# CLP_v1_2_Sch1.net
KiCad netlist of a schematic drawn in Altium Designer
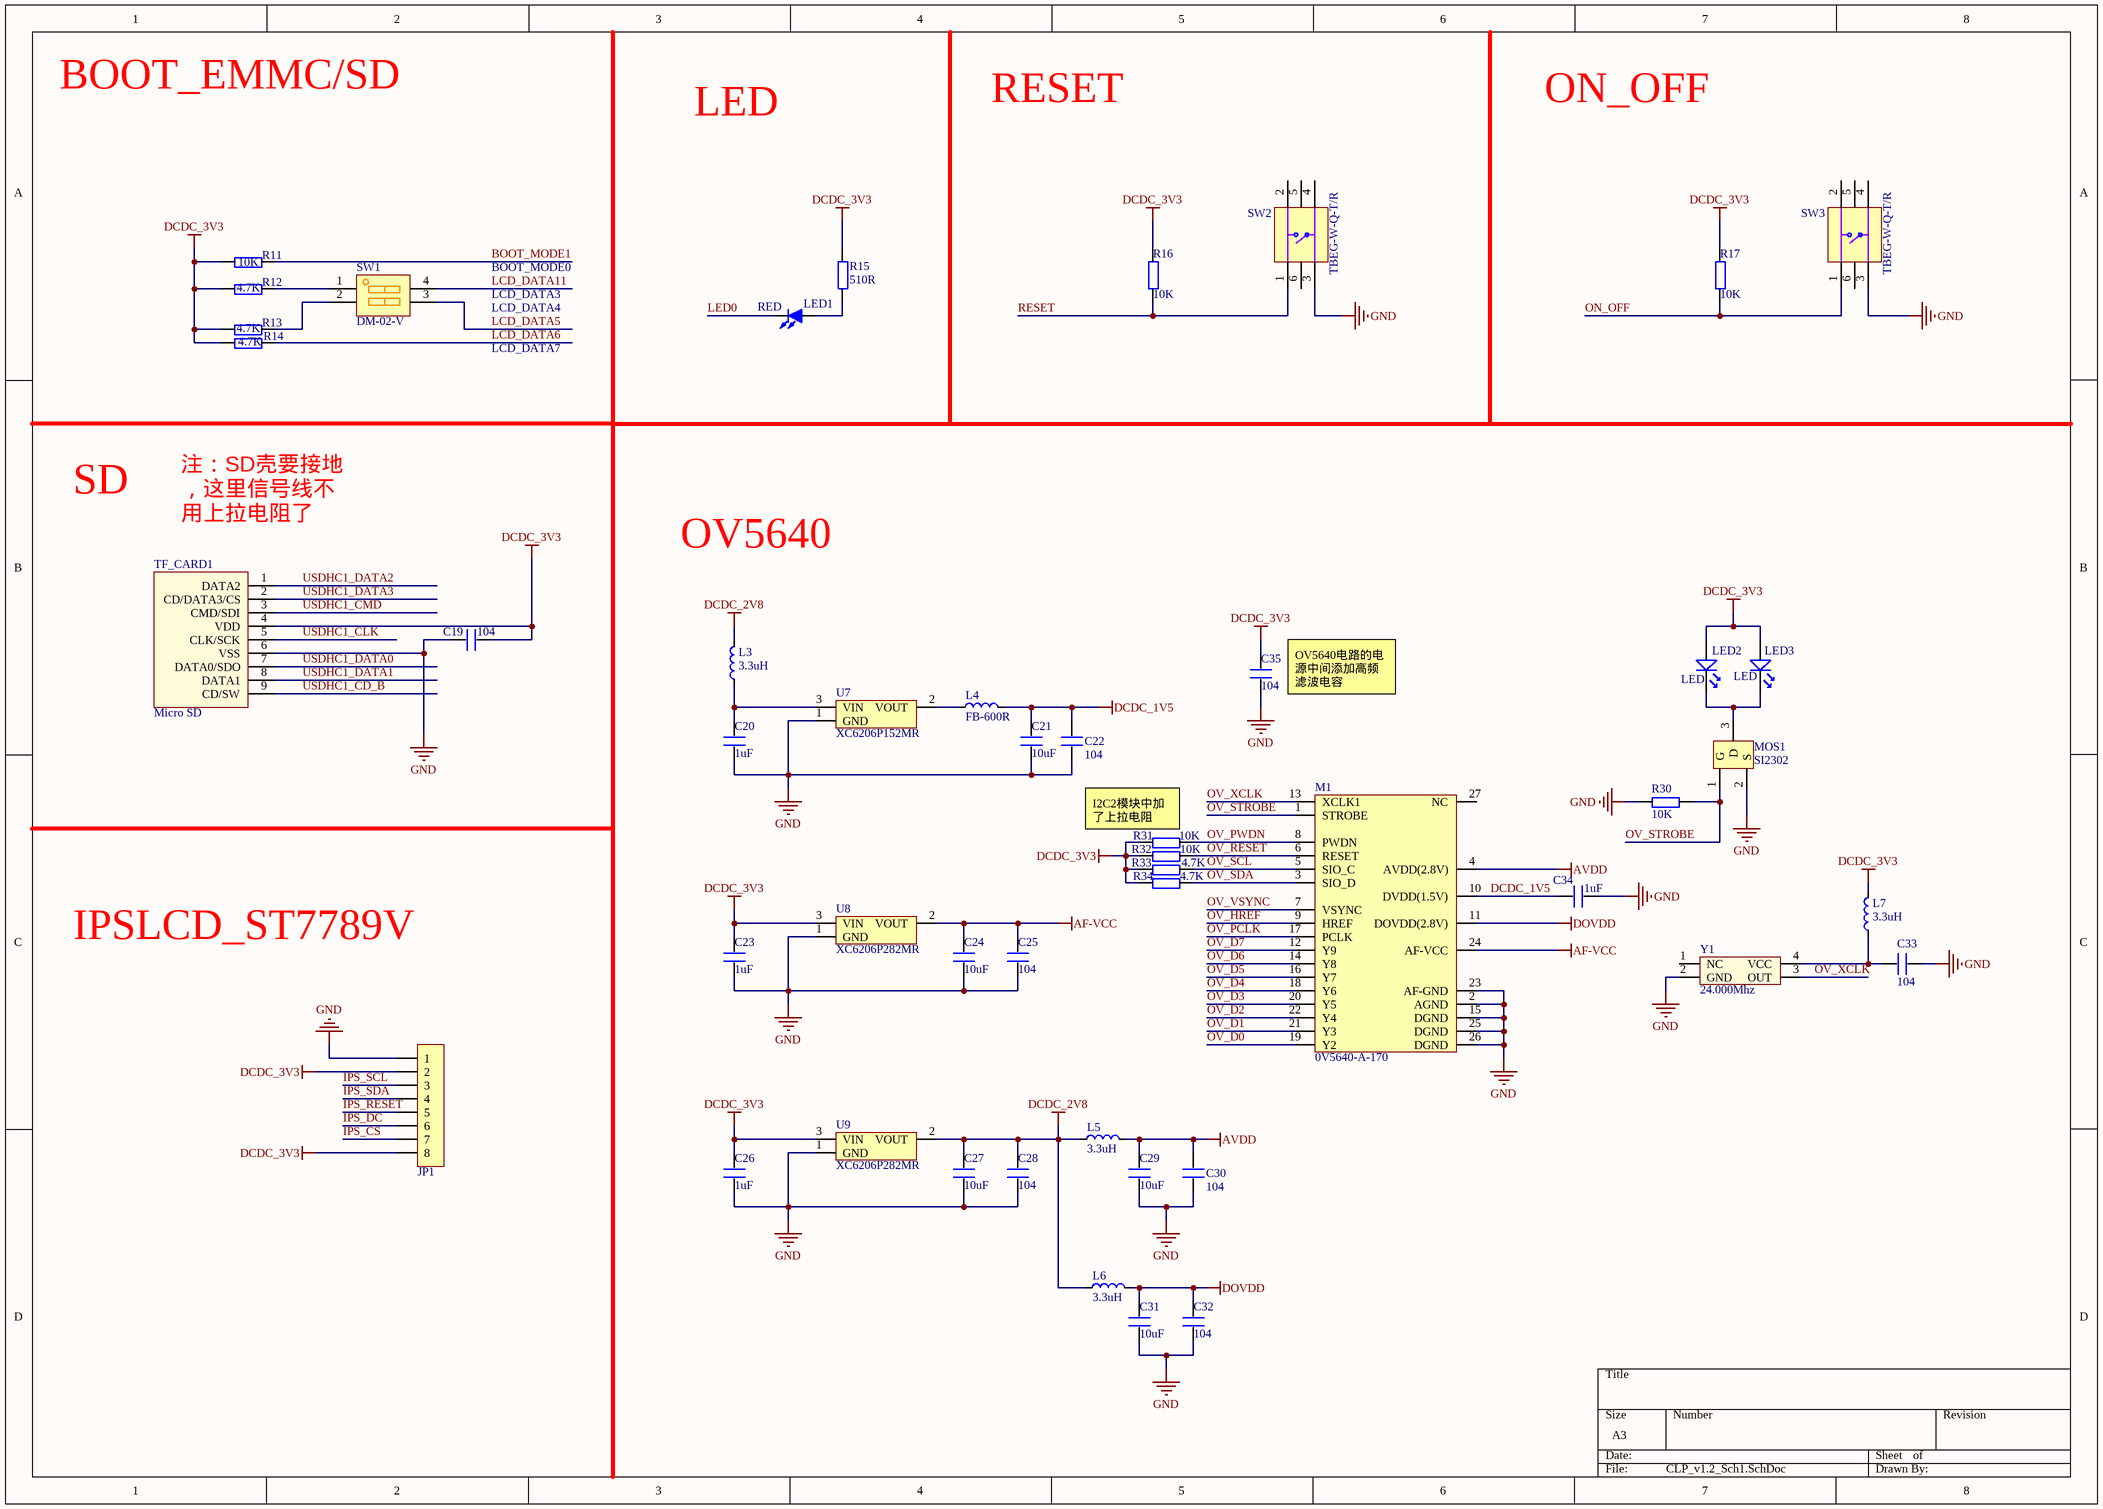
[diagram p0: CLP_v1.2_Sch1.SchDoc]

(export (version "E")
  (design (tool "Eeschema 10.0.6"))
  (components
    (comp (ref "C19") (value "104") (footprint "C 0603") (libsource (lib "IMX6UL_ALPHA(底板)_V2.0") (part "C")))
    (comp (ref "C20") (value "1uF") (footprint "C 0603") (libsource (lib "IMX6UL_ALPHA(底板)_V2.0") (part "C")))
    (comp (ref "C21")
      (value "10uF")
      (footprint "C 0603")
      (libsource (lib "IMX6UL_ALPHA(底板)_V2.0") (part "C"))
    )
    (comp (ref "C22") (value "104") (footprint "C 0603") (libsource (lib "IMX6UL_ALPHA(底板)_V2.0") (part "C")))
    (comp (ref "C23") (value "1uF") (footprint "C 0603") (libsource (lib "IMX6UL_ALPHA(底板)_V2.0") (part "C")))
    (comp (ref "C24")
      (value "10uF")
      (footprint "C 0603")
      (libsource (lib "IMX6UL_ALPHA(底板)_V2.0") (part "C"))
    )
    (comp (ref "C25") (value "104") (footprint "C 0603") (libsource (lib "IMX6UL_ALPHA(底板)_V2.0") (part "C")))
    (comp (ref "C26") (value "1uF") (footprint "C 0603") (libsource (lib "IMX6UL_ALPHA(底板)_V2.0") (part "C")))
    (comp (ref "C27")
      (value "10uF")
      (footprint "C 0603")
      (libsource (lib "IMX6UL_ALPHA(底板)_V2.0") (part "C"))
    )
    (comp (ref "C28") (value "104") (footprint "C 0603") (libsource (lib "IMX6UL_ALPHA(底板)_V2.0") (part "C")))
    (comp (ref "C29")
      (value "10uF")
      (footprint "C 0603")
      (libsource (lib "IMX6UL_ALPHA(底板)_V2.0") (part "C"))
    )
    (comp (ref "C30") (value "104") (footprint "C 0603") (libsource (lib "IMX6UL_ALPHA(底板)_V2.0") (part "C")))
    (comp (ref "C31")
      (value "10uF")
      (footprint "C 0603")
      (libsource (lib "IMX6UL_ALPHA(底板)_V2.0") (part "C"))
    )
    (comp (ref "C32") (value "104") (footprint "C 0603") (libsource (lib "IMX6UL_ALPHA(底板)_V2.0") (part "C")))
    (comp (ref "C33") (value "104") (footprint "C 0603") (libsource (lib "IMX6UL_ALPHA(底板)_V2.0") (part "C")))
    (comp (ref "C34") (value "1uF") (footprint "C 0603") (libsource (lib "IMX6UL_ALPHA(底板)_V2.0") (part "C")))
    (comp (ref "C35") (value "104") (footprint "C 0603") (libsource (lib "IMX6UL_ALPHA(底板)_V2.0") (part "C")))
    (comp (ref "JP1")
      (value "HDR-1X8")
      (footprint "HDR-1X8_M")
      (description "8P接插件")
      (fields (field (name "版权归属") "黎明电子style"))
      (libsource (lib "排针_排母") (part "Header 8"))
    )
    (comp (ref "L3")
      (value "3.3uH")
      (footprint "L 0603")
      (description "小功率贴片电感磁珠")
      (fields (field (name "版权归属") "源创客"))
      (libsource (lib "IMX6UL_ALPHA(底板)_V2.0") (part "L"))
    )
    (comp (ref "L4")
      (value "FB-600R")
      (footprint "L 0603")
      (description "小功率贴片电感磁珠")
      (fields (field (name "版权归属") "源创客"))
      (libsource (lib "IMX6UL_ALPHA(底板)_V2.0") (part "L"))
    )
    (comp (ref "L5")
      (value "3.3uH")
      (footprint "L 0603")
      (description "小功率贴片电感磁珠")
      (fields (field (name "版权归属") "源创客"))
      (libsource (lib "IMX6UL_ALPHA(底板)_V2.0") (part "L"))
    )
    (comp (ref "L6")
      (value "3.3uH")
      (footprint "L 0603")
      (description "小功率贴片电感磁珠")
      (fields (field (name "版权归属") "源创客"))
      (libsource (lib "IMX6UL_ALPHA(底板)_V2.0") (part "L"))
    )
    (comp (ref "L7")
      (value "3.3uH")
      (footprint "L 0603")
      (description "小功率贴片电感磁珠")
      (fields (field (name "版权归属") "源创客"))
      (libsource (lib "IMX6UL_ALPHA(底板)_V2.0") (part "L"))
    )
    (comp (ref "LED1")
      (value "RED")
      (footprint "LED 0805R")
      (description "贴片LED")
      (fields (field (name "版权归属") "源创客"))
      (libsource (lib "IMX6UL_ALPHA(底板)_V2.0") (part "LED-SMD"))
    )
    (comp (ref "LED2") (value "LED") (footprint "SMDLED-3528") (libsource (lib "OV5460") (part "LED")))
    (comp (ref "LED3") (value "LED") (footprint "SMDLED-3528") (libsource (lib "OV5460") (part "LED")))
    (comp (ref "M1")
      (value "0V5640-A-170")
      (footprint "OV5640")
      (description "OV5640-A-170,AF,FPC")
      (libsource (lib "OV5460") (part "OV5640-A-170"))
    )
    (comp (ref "MOS1")
      (value "SI2302")
      (footprint "SO-G3/C2.5")
      (description "AP2306")
      (libsource (lib "OV5460") (part "MOS-N"))
    )
    (comp (ref "R11") (value "10K") (footprint "R 0603") (libsource (lib "IMX6UL_ALPHA(底板)_V2.0") (part "R")))
    (comp (ref "R12")
      (value "4.7K")
      (footprint "R 0603")
      (libsource (lib "IMX6UL_ALPHA(底板)_V2.0") (part "R"))
    )
    (comp (ref "R13")
      (value "4.7K")
      (footprint "R 0603")
      (libsource (lib "IMX6UL_ALPHA(底板)_V2.0") (part "R"))
    )
    (comp (ref "R14")
      (value "4.7K")
      (footprint "R 0603")
      (libsource (lib "IMX6UL_ALPHA(底板)_V2.0") (part "R"))
    )
    (comp (ref "R15")
      (value "510R")
      (footprint "R 0603")
      (libsource (lib "IMX6UL_ALPHA(底板)_V2.0") (part "R"))
    )
    (comp (ref "R16") (value "10K") (footprint "R 0603") (libsource (lib "IMX6UL_ALPHA(底板)_V2.0") (part "R")))
    (comp (ref "R17") (value "10K") (footprint "R 0603") (libsource (lib "IMX6UL_ALPHA(底板)_V2.0") (part "R")))
    (comp (ref "R30") (value "10K") (footprint "R 0603") (libsource (lib "IMX6UL_ALPHA(底板)_V2.0") (part "R")))
    (comp (ref "R31") (value "10K") (footprint "R 0603") (libsource (lib "IMX6UL_ALPHA(底板)_V2.0") (part "R")))
    (comp (ref "R32") (value "10K") (footprint "R 0603") (libsource (lib "IMX6UL_ALPHA(底板)_V2.0") (part "R")))
    (comp (ref "R33")
      (value "4.7K")
      (footprint "R 0603")
      (libsource (lib "IMX6UL_ALPHA(底板)_V2.0") (part "R"))
    )
    (comp (ref "R34")
      (value "4.7K")
      (footprint "R 0603")
      (libsource (lib "IMX6UL_ALPHA(底板)_V2.0") (part "R"))
    )
    (comp (ref "SW1")
      (value "DM-02-V")
      (footprint "SMD_KEY")
      (description "boot && led key")
      (libsource (lib "CLP_v1.2_SchLib") (part "SMD_KEY"))
    )
    (comp (ref "SW2")
      (value "TBEG-W-Q-T/R")
      (footprint "SW")
      (description "key")
      (libsource (lib "CLP_v1.2_SchLib") (part "SW"))
    )
    (comp (ref "SW3")
      (value "TBEG-W-Q-T/R")
      (footprint "SW")
      (description "key")
      (libsource (lib "CLP_v1.2_SchLib") (part "SW"))
    )
    (comp (ref "TF_CARD1")
      (value "Micro SD")
      (footprint "Micro SD")
      (description "Micro SD卡")
      (fields (field (name "版权归属") "源创客"))
      (libsource (lib "IMX6UL_ALPHA(底板)_V2.0") (part "Micro SD"))
    )
    (comp (ref "U7")
      (value "XC6206P152MR")
      (footprint "SOT-23")
      (description "LDO,SOT23,1.2~5.0V")
      (libsource (lib "OV5460") (part "XC6206"))
    )
    (comp (ref "U8")
      (value "XC6206P282MR")
      (footprint "SOT-23")
      (description "LDO,SOT23,1.2~5.0V")
      (libsource (lib "OV5460") (part "XC6206"))
    )
    (comp (ref "U9")
      (value "XC6206P282MR")
      (footprint "SOT-23")
      (description "LDO,SOT23,1.2~5.0V")
      (libsource (lib "OV5460") (part "XC6206"))
    )
    (comp (ref "Y1")
      (value "24.000Mhz")
      (footprint "XTAL3225")
      (description "有源晶振")
      (libsource (lib "OV5460") (part "XTAL_S"))
    )
  )
  (nets
    (net (code "1") (name "/BOOT_MODE1") (class "Default") (node (ref "R11") (pin "2") (pintype "passive")))
    (net (code "2") (name "/IPS_CS") (class "Default")
      (node (ref "JP1") (pin "7") (pinfunction "7_7") (pintype "passive"))
    )
    (net (code "3") (name "/IPS_DC") (class "Default")
      (node (ref "JP1") (pin "6") (pinfunction "6_6") (pintype "passive"))
    )
    (net (code "4") (name "/IPS_RESET") (class "Default")
      (node (ref "JP1") (pin "5") (pinfunction "5_5") (pintype "passive"))
    )
    (net (code "5") (name "/IPS_SCL") (class "Default")
      (node (ref "JP1") (pin "3") (pinfunction "3_3") (pintype "passive"))
    )
    (net (code "6") (name "/IPS_SDA") (class "Default")
      (node (ref "JP1") (pin "4") (pinfunction "4_4") (pintype "passive"))
    )
    (net (code "7") (name "/LCD_DATA5") (class "Default")
      (node (ref "SW1") (pin "3") (pinfunction "3_3") (pintype "passive"))
    )
    (net (code "8") (name "/LCD_DATA6") (class "Default") (node (ref "R14") (pin "2") (pintype "passive")))
    (net (code "9") (name "/LCD_DATA11") (class "Default")
      (node (ref "SW1") (pin "4") (pinfunction "4_4") (pintype "passive"))
    )
    (net (code "10") (name "/LED0") (class "Default")
      (node (ref "LED1") (pin "2") (pinfunction "K_2") (pintype "passive"))
    )
    (net (code "11") (name "/ON_OFF") (class "Default")
      (node (ref "R17") (pin "1") (pintype "passive"))
      (node (ref "SW3") (pin "1") (pinfunction "1_1") (pintype "passive"))
    )
    (net (code "12") (name "/OV_D0") (class "Default")
      (node (ref "M1") (pin "19") (pinfunction "Y2_19") (pintype "passive"))
    )
    (net (code "13") (name "/OV_D1") (class "Default")
      (node (ref "M1") (pin "21") (pinfunction "Y3_21") (pintype "passive"))
    )
    (net (code "14") (name "/OV_D2") (class "Default")
      (node (ref "M1") (pin "22") (pinfunction "Y4_22") (pintype "passive"))
    )
    (net (code "15") (name "/OV_D3") (class "Default")
      (node (ref "M1") (pin "20") (pinfunction "Y5_20") (pintype "passive"))
    )
    (net (code "16") (name "/OV_D4") (class "Default")
      (node (ref "M1") (pin "18") (pinfunction "Y6_18") (pintype "passive"))
    )
    (net (code "17") (name "/OV_D5") (class "Default")
      (node (ref "M1") (pin "16") (pinfunction "Y7_16") (pintype "passive"))
    )
    (net (code "18") (name "/OV_D6") (class "Default")
      (node (ref "M1") (pin "14") (pinfunction "Y8_14") (pintype "passive"))
    )
    (net (code "19") (name "/OV_D7") (class "Default")
      (node (ref "M1") (pin "12") (pinfunction "Y9_12") (pintype "passive"))
    )
    (net (code "20") (name "/OV_HREF") (class "Default")
      (node (ref "M1") (pin "9") (pinfunction "HREF_9") (pintype "passive"))
    )
    (net (code "21") (name "/OV_PCLK") (class "Default")
      (node (ref "M1") (pin "17") (pinfunction "PCLK_17") (pintype "passive"))
    )
    (net (code "22") (name "/OV_PWDN") (class "Default")
      (node (ref "M1") (pin "8") (pinfunction "PWDN_8") (pintype "passive"))
      (node (ref "R31") (pin "2") (pintype "passive"))
    )
    (net (code "23") (name "/OV_RESET") (class "Default")
      (node (ref "M1") (pin "6") (pinfunction "RESET_6") (pintype "passive"))
      (node (ref "R32") (pin "2") (pintype "passive"))
    )
    (net (code "24") (name "/OV_SCL") (class "Default")
      (node (ref "M1") (pin "5") (pinfunction "SIO_C_5") (pintype "passive"))
      (node (ref "R33") (pin "2") (pintype "passive"))
    )
    (net (code "25") (name "/OV_SDA") (class "Default")
      (node (ref "M1") (pin "3") (pinfunction "SIO_D_3") (pintype "passive"))
      (node (ref "R34") (pin "2") (pintype "passive"))
    )
    (net (code "26") (name "/OV_STROBE") (class "Default")
      (node (ref "M1") (pin "1") (pinfunction "STROBE_1") (pintype "passive"))
      (node (ref "MOS1") (pin "1") (pinfunction "G_1") (pintype "passive"))
      (node (ref "R30") (pin "2") (pintype "passive"))
    )
    (net (code "27") (name "/OV_VSYNC") (class "Default")
      (node (ref "M1") (pin "7") (pinfunction "VSYNC_7") (pintype "passive"))
    )
    (net (code "28") (name "/OV_XCLK") (class "Default")
      (node (ref "M1") (pin "13") (pinfunction "XCLK1_13") (pintype "passive"))
      (node (ref "Y1") (pin "3") (pinfunction "OUT_3") (pintype "passive"))
    )
    (net (code "29") (name "/RESET") (class "Default")
      (node (ref "R16") (pin "1") (pintype "passive"))
      (node (ref "SW2") (pin "1") (pinfunction "1_1") (pintype "passive"))
    )
    (net (code "30") (name "/USDHC1_CD_B") (class "Default")
      (node (ref "TF_CARD1") (pin "9") (pinfunction "CD/SW_9") (pintype "passive"))
    )
    (net (code "31") (name "/USDHC1_CLK") (class "Default")
      (node (ref "TF_CARD1") (pin "5") (pinfunction "CLK/SCK_5") (pintype "passive"))
    )
    (net (code "32") (name "/USDHC1_CMD") (class "Default")
      (node (ref "TF_CARD1") (pin "3") (pinfunction "CMD/SDI_3") (pintype "passive"))
    )
    (net (code "33") (name "/USDHC1_DATA0") (class "Default")
      (node (ref "TF_CARD1") (pin "7") (pinfunction "DATA0/SDO_7") (pintype "passive"))
    )
    (net (code "34") (name "/USDHC1_DATA1") (class "Default")
      (node (ref "TF_CARD1") (pin "8") (pinfunction "DATA1_8") (pintype "passive"))
    )
    (net (code "35") (name "/USDHC1_DATA2") (class "Default")
      (node (ref "TF_CARD1") (pin "1") (pinfunction "DATA2_1") (pintype "passive"))
    )
    (net (code "36") (name "/USDHC1_DATA3") (class "Default")
      (node (ref "TF_CARD1") (pin "2") (pinfunction "CD/DATA3/CS_2") (pintype "passive"))
    )
    (net (code "37") (name "AF-VCC") (class "Default")
      (node (ref "C24") (pin "2") (pintype "passive"))
      (node (ref "C25") (pin "2") (pintype "passive"))
      (node (ref "M1") (pin "24") (pinfunction "AF-VCC_24") (pintype "passive"))
      (node (ref "U8") (pin "2") (pinfunction "VOUT_2") (pintype "passive"))
    )
    (net (code "38") (name "AVDD") (class "Default")
      (node (ref "C29") (pin "2") (pintype "passive"))
      (node (ref "C30") (pin "2") (pintype "passive"))
      (node (ref "L5") (pin "2") (pinfunction "2_2") (pintype "passive"))
      (node (ref "M1") (pin "4") (pinfunction "AVDD(2.8V)_4") (pintype "passive"))
    )
    (net (code "39") (name "DCDC_1V5") (class "Default")
      (node (ref "C21") (pin "2") (pintype "passive"))
      (node (ref "C22") (pin "2") (pintype "passive"))
      (node (ref "C34") (pin "1") (pintype "passive"))
      (node (ref "L4") (pin "2") (pinfunction "2_2") (pintype "passive"))
      (node (ref "M1") (pin "10") (pinfunction "DVDD(1.5V)_10") (pintype "passive"))
    )
    (net (code "40") (name "DCDC_2V8") (class "Default")
      (node (ref "C27") (pin "2") (pintype "passive"))
      (node (ref "C28") (pin "2") (pintype "passive"))
      (node (ref "L3") (pin "2") (pinfunction "2_2") (pintype "passive"))
      (node (ref "L5") (pin "1") (pinfunction "1_1") (pintype "passive"))
      (node (ref "L6") (pin "1") (pinfunction "1_1") (pintype "passive"))
      (node (ref "U9") (pin "2") (pinfunction "VOUT_2") (pintype "passive"))
    )
    (net (code "41") (name "DCDC_3V3") (class "Default")
      (node (ref "C19") (pin "2") (pintype "passive"))
      (node (ref "C23") (pin "2") (pintype "passive"))
      (node (ref "C26") (pin "2") (pintype "passive"))
      (node (ref "C35") (pin "2") (pintype "passive"))
      (node (ref "JP1") (pin "2") (pinfunction "2_2") (pintype "passive"))
      (node (ref "JP1") (pin "8") (pinfunction "8_8") (pintype "passive"))
      (node (ref "L7") (pin "2") (pinfunction "2_2") (pintype "passive"))
      (node (ref "LED2") (pin "1") (pinfunction "1_1") (pintype "passive"))
      (node (ref "LED3") (pin "1") (pinfunction "1_1") (pintype "passive"))
      (node (ref "R11") (pin "1") (pintype "passive"))
      (node (ref "R12") (pin "1") (pintype "passive"))
      (node (ref "R13") (pin "1") (pintype "passive"))
      (node (ref "R14") (pin "1") (pintype "passive"))
      (node (ref "R15") (pin "2") (pintype "passive"))
      (node (ref "R16") (pin "2") (pintype "passive"))
      (node (ref "R17") (pin "2") (pintype "passive"))
      (node (ref "R31") (pin "1") (pintype "passive"))
      (node (ref "R32") (pin "1") (pintype "passive"))
      (node (ref "R33") (pin "1") (pintype "passive"))
      (node (ref "R34") (pin "1") (pintype "passive"))
      (node (ref "TF_CARD1") (pin "4") (pinfunction "VDD_4") (pintype "passive"))
      (node (ref "U8") (pin "3") (pinfunction "VIN_3") (pintype "passive"))
      (node (ref "U9") (pin "3") (pinfunction "VIN_3") (pintype "passive"))
    )
    (net (code "42") (name "DOVDD") (class "Default")
      (node (ref "C31") (pin "2") (pintype "passive"))
      (node (ref "C32") (pin "2") (pintype "passive"))
      (node (ref "L6") (pin "2") (pinfunction "2_2") (pintype "passive"))
      (node (ref "M1") (pin "11") (pinfunction "DOVDD(2.8V)_11") (pintype "passive"))
    )
    (net (code "43") (name "GND") (class "Default")
      (node (ref "C19") (pin "1") (pintype "passive"))
      (node (ref "C20") (pin "1") (pintype "passive"))
      (node (ref "C21") (pin "1") (pintype "passive"))
      (node (ref "C22") (pin "1") (pintype "passive"))
      (node (ref "C23") (pin "1") (pintype "passive"))
      (node (ref "C24") (pin "1") (pintype "passive"))
      (node (ref "C25") (pin "1") (pintype "passive"))
      (node (ref "C26") (pin "1") (pintype "passive"))
      (node (ref "C27") (pin "1") (pintype "passive"))
      (node (ref "C28") (pin "1") (pintype "passive"))
      (node (ref "C29") (pin "1") (pintype "passive"))
      (node (ref "C30") (pin "1") (pintype "passive"))
      (node (ref "C31") (pin "1") (pintype "passive"))
      (node (ref "C32") (pin "1") (pintype "passive"))
      (node (ref "C33") (pin "2") (pintype "passive"))
      (node (ref "C34") (pin "2") (pintype "passive"))
      (node (ref "C35") (pin "1") (pintype "passive"))
      (node (ref "JP1") (pin "1") (pinfunction "1_1") (pintype "passive"))
      (node (ref "M1") (pin "15") (pinfunction "DGND_15") (pintype "passive"))
      (node (ref "M1") (pin "2") (pinfunction "AGND_2") (pintype "passive"))
      (node (ref "M1") (pin "23") (pinfunction "AF-GND_23") (pintype "passive"))
      (node (ref "M1") (pin "25") (pinfunction "DGND_25") (pintype "passive"))
      (node (ref "M1") (pin "26") (pinfunction "DGND_26") (pintype "passive"))
      (node (ref "MOS1") (pin "2") (pinfunction "S_2") (pintype "passive"))
      (node (ref "R30") (pin "1") (pintype "passive"))
      (node (ref "SW2") (pin "3") (pinfunction "3_3") (pintype "passive"))
      (node (ref "SW3") (pin "3") (pinfunction "3_3") (pintype "passive"))
      (node (ref "TF_CARD1") (pin "6") (pinfunction "VSS_6") (pintype "passive"))
      (node (ref "U7") (pin "1") (pinfunction "GND_1") (pintype "passive"))
      (node (ref "U8") (pin "1") (pinfunction "GND_1") (pintype "passive"))
      (node (ref "U9") (pin "1") (pinfunction "GND_1") (pintype "passive"))
      (node (ref "Y1") (pin "2") (pinfunction "GND_2") (pintype "passive"))
    )
    (net (code "44") (name "Net-(LED1-A)") (class "Default")
      (node (ref "LED1") (pin "1") (pinfunction "A_1") (pintype "passive"))
      (node (ref "R15") (pin "1") (pintype "passive"))
    )
    (net (code "45") (name "Net-(MOS1-D)") (class "Default")
      (node (ref "LED2") (pin "2") (pinfunction "2_2") (pintype "passive"))
      (node (ref "LED3") (pin "2") (pinfunction "2_2") (pintype "passive"))
      (node (ref "MOS1") (pin "3") (pinfunction "D_3") (pintype "passive"))
    )
    (net (code "46") (name "Net-(R12-Pad2)") (class "Default")
      (node (ref "R12") (pin "2") (pintype "passive"))
      (node (ref "SW1") (pin "1") (pinfunction "1_1") (pintype "passive"))
    )
    (net (code "47") (name "Net-(R13-Pad2)") (class "Default")
      (node (ref "R13") (pin "2") (pintype "passive"))
      (node (ref "SW1") (pin "2") (pinfunction "2_2") (pintype "passive"))
    )
    (net (code "48") (name "Net-(U7-VIN)") (class "Default")
      (node (ref "C20") (pin "2") (pintype "passive"))
      (node (ref "L3") (pin "1") (pinfunction "1_1") (pintype "passive"))
      (node (ref "U7") (pin "3") (pinfunction "VIN_3") (pintype "passive"))
    )
    (net (code "49") (name "Net-(U7-VOUT)") (class "Default")
      (node (ref "L4") (pin "1") (pinfunction "1_1") (pintype "passive"))
      (node (ref "U7") (pin "2") (pinfunction "VOUT_2") (pintype "passive"))
    )
    (net (code "50") (name "Net-(Y1-VCC)") (class "Default")
      (node (ref "C33") (pin "1") (pintype "passive"))
      (node (ref "L7") (pin "1") (pinfunction "1_1") (pintype "passive"))
      (node (ref "Y1") (pin "4") (pinfunction "VCC_4") (pintype "passive"))
    )
    (net (code "51") (name "unconnected-(M1-NC-Pad27)") (class "Default")
      (node (ref "M1") (pin "27") (pinfunction "NC_27") (pintype "passive"))
    )
    (net (code "52") (name "unconnected-(SW2-Pad2)") (class "Default")
      (node (ref "SW2") (pin "2") (pinfunction "2_2") (pintype "passive"))
    )
    (net (code "53") (name "unconnected-(SW2-Pad4)") (class "Default")
      (node (ref "SW2") (pin "4") (pinfunction "4_4") (pintype "passive"))
    )
    (net (code "54") (name "unconnected-(SW2-Pad5)") (class "Default")
      (node (ref "SW2") (pin "5") (pinfunction "5_5") (pintype "passive"))
    )
    (net (code "55") (name "unconnected-(SW2-Pad6)") (class "Default")
      (node (ref "SW2") (pin "6") (pinfunction "6_6") (pintype "passive"))
    )
    (net (code "56") (name "unconnected-(SW3-Pad2)") (class "Default")
      (node (ref "SW3") (pin "2") (pinfunction "2_2") (pintype "passive"))
    )
    (net (code "57") (name "unconnected-(SW3-Pad4)") (class "Default")
      (node (ref "SW3") (pin "4") (pinfunction "4_4") (pintype "passive"))
    )
    (net (code "58") (name "unconnected-(SW3-Pad5)") (class "Default")
      (node (ref "SW3") (pin "5") (pinfunction "5_5") (pintype "passive"))
    )
    (net (code "59") (name "unconnected-(SW3-Pad6)") (class "Default")
      (node (ref "SW3") (pin "6") (pinfunction "6_6") (pintype "passive"))
    )
    (net (code "60") (name "unconnected-(Y1-NC-Pad1)") (class "Default")
      (node (ref "Y1") (pin "1") (pinfunction "NC_1") (pintype "passive"))
    )
  )
)
